# TheRightHandPathSVG.net
KiCad netlist of a schematic drawn in EAGLE
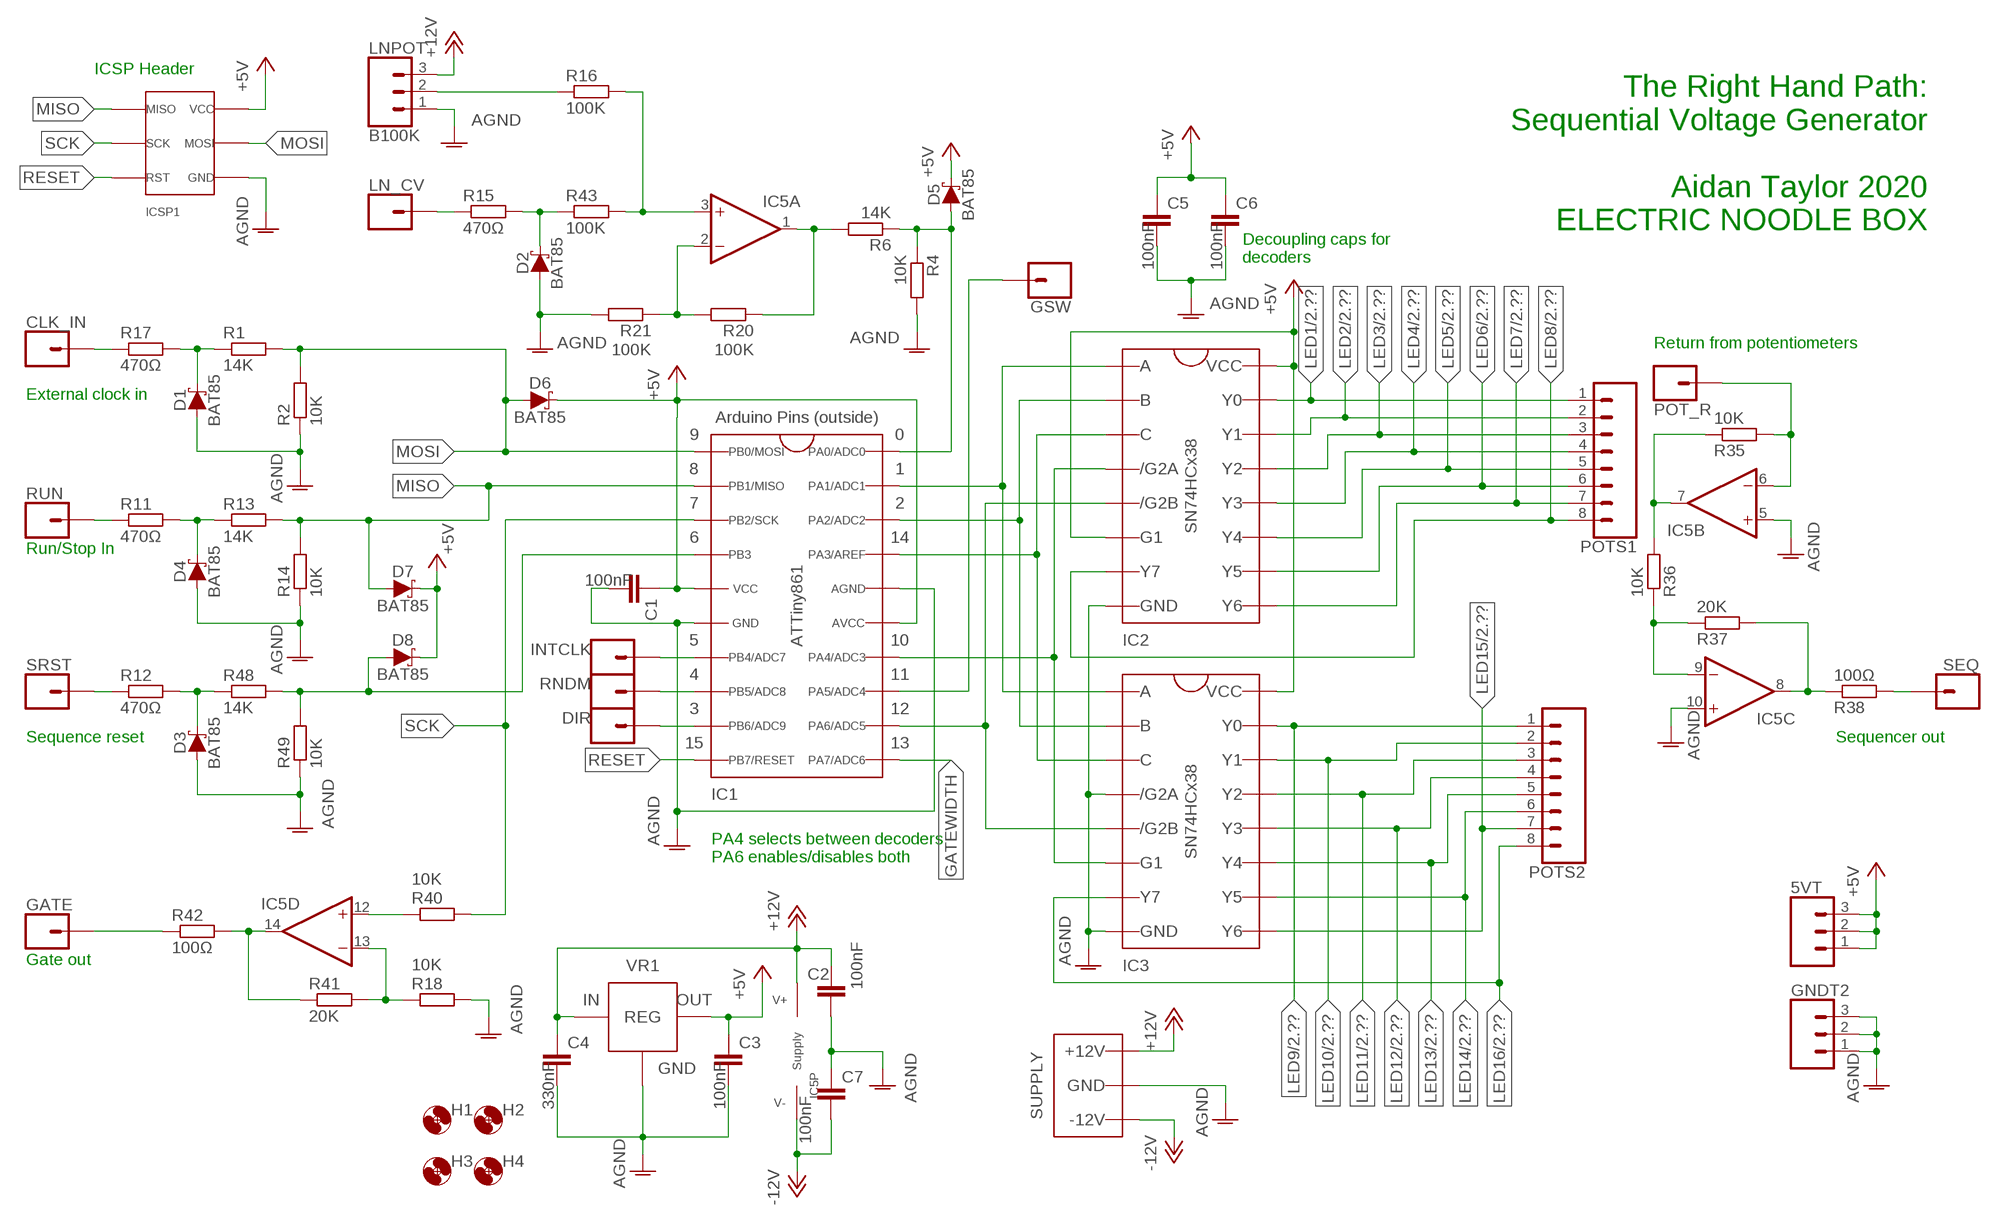
[diagram p0: schematic, sheet 1]
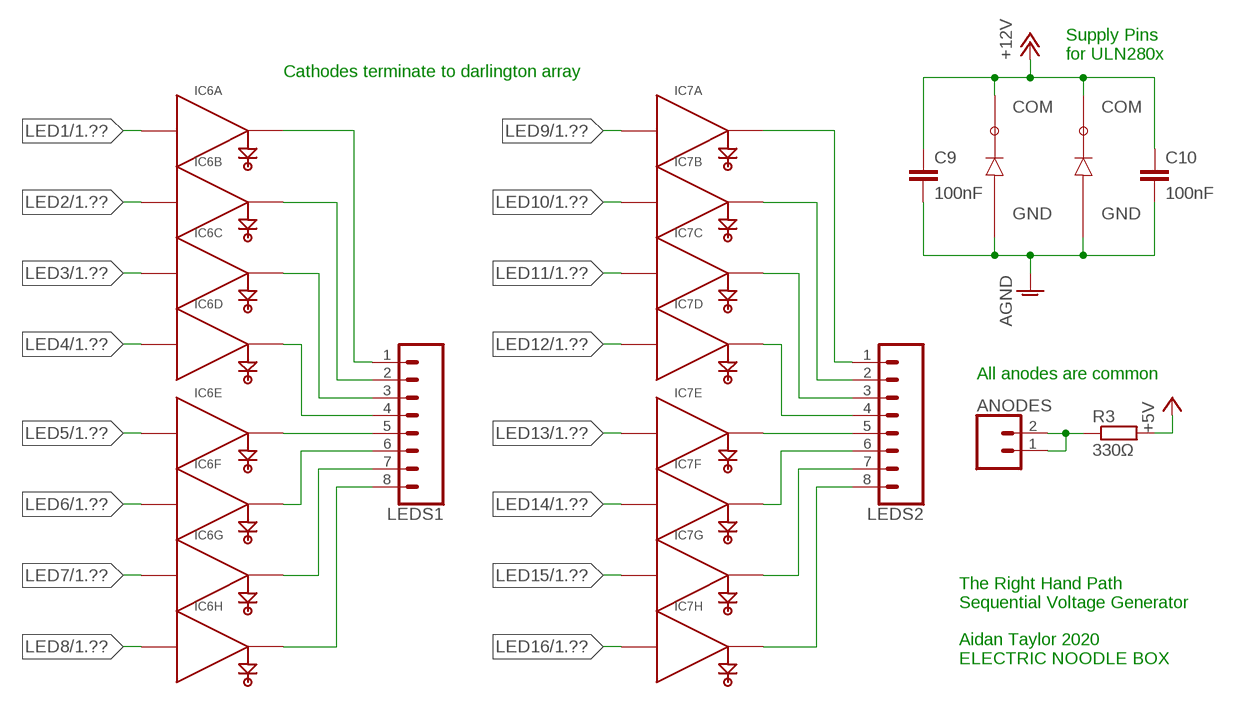
[diagram p1: schematic, sheet 2]

(export (version "E")
  (design (tool "Eeschema 10.0.6"))
  (components
    (comp (ref "5VT")
      (value "3XWIREPAD")
      (footprint "eagle-import:1X03")
      (libsource (lib "eagle-import") (part "3XWIREPAD"))
    )
    (comp (ref "C1")
      (value "100nF")
      (footprint "eagle-import:C050-025X075")
      (libsource (lib "eagle-import") (part "C-EU050-025X075"))
    )
    (comp (ref "C2")
      (value "100nF")
      (footprint "eagle-import:C050-025X075")
      (libsource (lib "eagle-import") (part "C-EU050-025X075"))
    )
    (comp (ref "C3")
      (value "100nF")
      (footprint "eagle-import:C050-025X075")
      (libsource (lib "eagle-import") (part "C-EU050-025X075"))
    )
    (comp (ref "C4")
      (value "330nF")
      (footprint "eagle-import:C050-025X075")
      (libsource (lib "eagle-import") (part "C-EU050-025X075"))
    )
    (comp (ref "C5")
      (value "100nF")
      (footprint "eagle-import:C050-025X075")
      (libsource (lib "eagle-import") (part "C-EU050-025X075"))
    )
    (comp (ref "C6")
      (value "100nF")
      (footprint "eagle-import:C050-025X075")
      (libsource (lib "eagle-import") (part "C-EU050-025X075"))
    )
    (comp (ref "C7")
      (value "100nF")
      (footprint "eagle-import:C050-025X075")
      (libsource (lib "eagle-import") (part "C-EU050-025X075"))
    )
    (comp (ref "CLK_IN")
      (value "1XWIREPAD")
      (footprint "eagle-import:1X01")
      (libsource (lib "eagle-import") (part "1XWIREPAD"))
    )
    (comp (ref "D1")
      (value "BAT85")
      (footprint "eagle-import:DO35-7")
      (libsource (lib "eagle-import") (part "SCHOTTKY_DO35"))
    )
    (comp (ref "D2")
      (value "BAT85")
      (footprint "eagle-import:DO35-7")
      (libsource (lib "eagle-import") (part "SCHOTTKY_DO35"))
    )
    (comp (ref "D3")
      (value "BAT85")
      (footprint "eagle-import:DO35-7")
      (libsource (lib "eagle-import") (part "SCHOTTKY_DO35"))
    )
    (comp (ref "D4")
      (value "BAT85")
      (footprint "eagle-import:DO35-7")
      (libsource (lib "eagle-import") (part "SCHOTTKY_DO35"))
    )
    (comp (ref "D5")
      (value "BAT85")
      (footprint "eagle-import:DO35-7")
      (libsource (lib "eagle-import") (part "SCHOTTKY_DO35"))
    )
    (comp (ref "D6")
      (value "BAT85")
      (footprint "eagle-import:DO35-7")
      (libsource (lib "eagle-import") (part "SCHOTTKY_DO35"))
    )
    (comp (ref "D7")
      (value "BAT85")
      (footprint "eagle-import:DO35-7")
      (libsource (lib "eagle-import") (part "SCHOTTKY_DO35"))
    )
    (comp (ref "D8")
      (value "BAT85")
      (footprint "eagle-import:DO35-7")
      (libsource (lib "eagle-import") (part "SCHOTTKY_DO35"))
    )
    (comp (ref "DIR")
      (value "1XWIREPAD")
      (footprint "eagle-import:1X01")
      (libsource (lib "eagle-import") (part "1XWIREPAD"))
    )
    (comp (ref "GATE")
      (value "1XWIREPAD")
      (footprint "eagle-import:1X01")
      (libsource (lib "eagle-import") (part "1XWIREPAD"))
    )
    (comp (ref "GNDT2")
      (value "3XWIREPAD")
      (footprint "eagle-import:1X03")
      (libsource (lib "eagle-import") (part "3XWIREPAD"))
    )
    (comp (ref "GSW")
      (value "1XWIREPAD")
      (footprint "eagle-import:1X01")
      (libsource (lib "eagle-import") (part "1XWIREPAD"))
    )
    (comp (ref "H1")
      (value "MOUNT-HOLE3.2")
      (footprint "eagle-import:3,2")
      (libsource (lib "eagle-import") (part "MOUNT-HOLE3.2"))
    )
    (comp (ref "H2")
      (value "MOUNT-HOLE3.2")
      (footprint "eagle-import:3,2")
      (libsource (lib "eagle-import") (part "MOUNT-HOLE3.2"))
    )
    (comp (ref "H3")
      (value "MOUNT-HOLE3.2")
      (footprint "eagle-import:3,2")
      (libsource (lib "eagle-import") (part "MOUNT-HOLE3.2"))
    )
    (comp (ref "H4")
      (value "MOUNT-HOLE3.2")
      (footprint "eagle-import:3,2")
      (libsource (lib "eagle-import") (part "MOUNT-HOLE3.2"))
    )
    (comp (ref "IC1")
      (value "ATTINY861")
      (footprint "eagle-import:DIL20")
      (libsource (lib "eagle-import") (part "ATTINY861"))
    )
    (comp (ref "IC2")
      (value "SN74HCX38")
      (footprint "eagle-import:DIL16")
      (libsource (lib "eagle-import") (part "SN74HCX38"))
    )
    (comp (ref "IC3")
      (value "SN74HCX38")
      (footprint "eagle-import:DIL16")
      (libsource (lib "eagle-import") (part "SN74HCX38"))
    )
    (comp (ref "IC5")
      (value "TL0X4DIL")
      (footprint "eagle-import:DIL14")
      (libsource (lib "eagle-import") (part "TL0X4DIL"))
    )
    (comp (ref "ICSP1")
      (value "ICSP_2.54")
      (footprint "eagle-import:2X3")
      (libsource (lib "eagle-import") (part "ICSP_2.54"))
    )
    (comp (ref "INTCLK")
      (value "1XWIREPAD")
      (footprint "eagle-import:1X01")
      (libsource (lib "eagle-import") (part "1XWIREPAD"))
    )
    (comp (ref "LNPOT")
      (value "B100K")
      (footprint "eagle-import:1X03")
      (libsource (lib "eagle-import") (part "3XWIREPAD"))
    )
    (comp (ref "LN_CV")
      (value "1XWIREPAD")
      (footprint "eagle-import:1X01")
      (libsource (lib "eagle-import") (part "1XWIREPAD"))
    )
    (comp (ref "POTS1")
      (value "8XWIREPAD")
      (footprint "eagle-import:1X08")
      (libsource (lib "eagle-import") (part "8XWIREPAD"))
    )
    (comp (ref "POTS2")
      (value "8XWIREPAD")
      (footprint "eagle-import:1X08")
      (libsource (lib "eagle-import") (part "8XWIREPAD"))
    )
    (comp (ref "POT_R")
      (value "1XWIREPAD")
      (footprint "eagle-import:1X01")
      (libsource (lib "eagle-import") (part "1XWIREPAD"))
    )
    (comp (ref "R1")
      (value "14K")
      (footprint "eagle-import:0207_10")
      (libsource (lib "eagle-import") (part "R-EU_0207/10"))
    )
    (comp (ref "R2")
      (value "10K")
      (footprint "eagle-import:0207_10")
      (libsource (lib "eagle-import") (part "R-EU_0207/10"))
    )
    (comp (ref "R4")
      (value "10K")
      (footprint "eagle-import:0207_10")
      (libsource (lib "eagle-import") (part "R-EU_0207/10"))
    )
    (comp (ref "R6")
      (value "14K")
      (footprint "eagle-import:0207_10")
      (libsource (lib "eagle-import") (part "R-EU_0207/10"))
    )
    (comp (ref "R11")
      (value "470Ω")
      (footprint "eagle-import:0207_10")
      (libsource (lib "eagle-import") (part "R-EU_0207/10"))
    )
    (comp (ref "R12")
      (value "470Ω")
      (footprint "eagle-import:0207_10")
      (libsource (lib "eagle-import") (part "R-EU_0207/10"))
    )
    (comp (ref "R13")
      (value "14K")
      (footprint "eagle-import:0207_10")
      (libsource (lib "eagle-import") (part "R-EU_0207/10"))
    )
    (comp (ref "R14")
      (value "10K")
      (footprint "eagle-import:0207_10")
      (libsource (lib "eagle-import") (part "R-EU_0207/10"))
    )
    (comp (ref "R15")
      (value "470Ω")
      (footprint "eagle-import:0207_10")
      (libsource (lib "eagle-import") (part "R-EU_0207/10"))
    )
    (comp (ref "R16")
      (value "100K")
      (footprint "eagle-import:0207_10")
      (libsource (lib "eagle-import") (part "R-EU_0207/10"))
    )
    (comp (ref "R17")
      (value "470Ω")
      (footprint "eagle-import:0207_10")
      (libsource (lib "eagle-import") (part "R-EU_0207/10"))
    )
    (comp (ref "R18")
      (value "10K")
      (footprint "eagle-import:0207_10")
      (libsource (lib "eagle-import") (part "R-EU_0207/10"))
    )
    (comp (ref "R20")
      (value "100K")
      (footprint "eagle-import:0207_10")
      (libsource (lib "eagle-import") (part "R-EU_0207/10"))
    )
    (comp (ref "R21")
      (value "100K")
      (footprint "eagle-import:0207_10")
      (libsource (lib "eagle-import") (part "R-EU_0207/10"))
    )
    (comp (ref "R35")
      (value "10K")
      (footprint "eagle-import:0207_10")
      (libsource (lib "eagle-import") (part "R-EU_0207/10"))
    )
    (comp (ref "R36")
      (value "10K")
      (footprint "eagle-import:0207_10")
      (libsource (lib "eagle-import") (part "R-EU_0207/10"))
    )
    (comp (ref "R37")
      (value "20K")
      (footprint "eagle-import:0207_10")
      (libsource (lib "eagle-import") (part "R-EU_0207/10"))
    )
    (comp (ref "R38")
      (value "100Ω")
      (footprint "eagle-import:0207_10")
      (libsource (lib "eagle-import") (part "R-EU_0207/10"))
    )
    (comp (ref "R40")
      (value "10K")
      (footprint "eagle-import:0207_10")
      (libsource (lib "eagle-import") (part "R-EU_0207/10"))
    )
    (comp (ref "R41")
      (value "20K")
      (footprint "eagle-import:0207_10")
      (libsource (lib "eagle-import") (part "R-EU_0207/10"))
    )
    (comp (ref "R42")
      (value "100Ω")
      (footprint "eagle-import:0207_10")
      (libsource (lib "eagle-import") (part "R-EU_0207/10"))
    )
    (comp (ref "R43")
      (value "100K")
      (footprint "eagle-import:0207_10")
      (libsource (lib "eagle-import") (part "R-EU_0207/10"))
    )
    (comp (ref "R48")
      (value "14K")
      (footprint "eagle-import:0207_10")
      (libsource (lib "eagle-import") (part "R-EU_0207/10"))
    )
    (comp (ref "R49")
      (value "10K")
      (footprint "eagle-import:0207_10")
      (libsource (lib "eagle-import") (part "R-EU_0207/10"))
    )
    (comp (ref "RNDM")
      (value "1XWIREPAD")
      (footprint "eagle-import:1X01")
      (libsource (lib "eagle-import") (part "1XWIREPAD"))
    )
    (comp (ref "RUN")
      (value "1XWIREPAD")
      (footprint "eagle-import:1X01")
      (libsource (lib "eagle-import") (part "1XWIREPAD"))
    )
    (comp (ref "SEQ")
      (value "1XWIREPAD")
      (footprint "eagle-import:1X01")
      (libsource (lib "eagle-import") (part "1XWIREPAD"))
    )
    (comp (ref "SRST")
      (value "1XWIREPAD")
      (footprint "eagle-import:1X01")
      (libsource (lib "eagle-import") (part "1XWIREPAD"))
    )
    (comp (ref "VR1")
      (value "L78L05TO92")
      (footprint "eagle-import:TO92")
      (libsource (lib "eagle-import") (part "L78L05TO92"))
    )
    (comp (ref "WP1")
      (value "COMBO_SUPPLY_HEADER")
      (footprint "eagle-import:COMBINED_POWER")
      (libsource (lib "eagle-import") (part "COMBO_SUPPLY_HEADER"))
    )
    (comp (ref "ANODES")
      (value "2XWIREPAD")
      (footprint "eagle-import:1X02")
      (libsource (lib "eagle-import") (part "2XWIREPAD"))
    )
    (comp (ref "C9")
      (value "100nF")
      (footprint "eagle-import:C050-025X075")
      (libsource (lib "eagle-import") (part "C-EU050-025X075"))
    )
    (comp (ref "C10")
      (value "100nF")
      (footprint "eagle-import:C050-025X075")
      (libsource (lib "eagle-import") (part "C-EU050-025X075"))
    )
    (comp (ref "IC6")
      (value "ULN2801")
      (footprint "eagle-import:DIL18")
      (libsource (lib "eagle-import") (part "ULN2801"))
    )
    (comp (ref "IC7")
      (value "ULN2801")
      (footprint "eagle-import:DIL18")
      (libsource (lib "eagle-import") (part "ULN2801"))
    )
    (comp (ref "LEDS1")
      (value "8XWIREPAD")
      (footprint "eagle-import:1X08")
      (libsource (lib "eagle-import") (part "8XWIREPAD"))
    )
    (comp (ref "LEDS2")
      (value "8XWIREPAD")
      (footprint "eagle-import:1X08")
      (libsource (lib "eagle-import") (part "8XWIREPAD"))
    )
    (comp (ref "R3")
      (value "330Ω")
      (footprint "eagle-import:0207_10")
      (libsource (lib "eagle-import") (part "R-EU_0207/10"))
    )
  )
  (nets
    (net (code "1") (name "+5V") (class "Default")
      (node (ref "5VT") (pin "1") (pinfunction "1_1") (pintype "passive"))
      (node (ref "5VT") (pin "2") (pinfunction "2_2") (pintype "passive"))
      (node (ref "5VT") (pin "3") (pinfunction "3_3") (pintype "passive"))
      (node (ref "C1") (pin "1") (pinfunction "1_1") (pintype "passive"))
      (node (ref "C3") (pin "1") (pinfunction "1_1") (pintype "passive"))
      (node (ref "C5") (pin "1") (pinfunction "1_1") (pintype "passive"))
      (node (ref "C6") (pin "1") (pinfunction "1_1") (pintype "passive"))
      (node (ref "D5") (pin "C") (pinfunction "C_C") (pintype "passive"))
      (node (ref "D6") (pin "C") (pinfunction "C_C") (pintype "passive"))
      (node (ref "D7") (pin "C") (pinfunction "C_C") (pintype "passive"))
      (node (ref "D8") (pin "C") (pinfunction "C_C") (pintype "passive"))
      (node (ref "IC1") (pin "15") (pinfunction "AVCC_15") (pintype "bidirectional"))
      (node (ref "IC1") (pin "5") (pinfunction "VCC_5") (pintype "power_in"))
      (node (ref "IC2") (pin "16") (pinfunction "16_VCC_16") (pintype "power_in"))
      (node (ref "IC2") (pin "6") (pinfunction "6_G1_6") (pintype "input"))
      (node (ref "IC3") (pin "16") (pinfunction "16_VCC_16") (pintype "power_in"))
      (node (ref "ICSP1") (pin "2") (pinfunction "6VCC_2") (pintype "power_in"))
      (node (ref "R3") (pin "2") (pinfunction "2_2") (pintype "passive"))
      (node (ref "VR1") (pin "1") (pinfunction "VOUT_1") (pintype "output"))
    )
    (net (code "2") (name "+12V") (class "Default")
      (node (ref "C10") (pin "1") (pinfunction "1_1") (pintype "passive"))
      (node (ref "C2") (pin "1") (pinfunction "1_1") (pintype "passive"))
      (node (ref "C4") (pin "1") (pinfunction "1_1") (pintype "passive"))
      (node (ref "C9") (pin "1") (pinfunction "1_1") (pintype "passive"))
      (node (ref "IC5") (pin "4") (pinfunction "V+_4") (pintype "bidirectional"))
      (node (ref "IC6") (pin "10") (pinfunction "COM_10") (pintype "power_in"))
      (node (ref "IC7") (pin "10") (pinfunction "COM_10") (pintype "power_in"))
      (node (ref "LNPOT") (pin "3") (pinfunction "3_3") (pintype "passive"))
      (node (ref "VR1") (pin "3") (pinfunction "VIN_3") (pintype "input"))
      (node (ref "WP1") (pin "V+1") (pinfunction "V++_V+1") (pintype "power_in"))
      (node (ref "WP1") (pin "V+2") (pinfunction "V++_V+2") (pintype "power_in"))
      (node (ref "WP1") (pin "V+3") (pinfunction "V++_V+3") (pintype "power_in"))
    )
    (net (code "3") (name "-12V") (class "Default")
      (node (ref "C7") (pin "2") (pinfunction "2_2") (pintype "passive"))
      (node (ref "IC5") (pin "11") (pinfunction "V-_11") (pintype "bidirectional"))
      (node (ref "WP1") (pin "V-1") (pinfunction "V--_V-1") (pintype "power_in"))
      (node (ref "WP1") (pin "V-2") (pinfunction "V--_V-2") (pintype "power_in"))
      (node (ref "WP1") (pin "V-3") (pinfunction "V--_V-3") (pintype "power_in"))
    )
    (net (code "4") (name "AGND") (class "Default")
      (node (ref "C1") (pin "2") (pinfunction "2_2") (pintype "passive"))
      (node (ref "C10") (pin "2") (pinfunction "2_2") (pintype "passive"))
      (node (ref "C2") (pin "2") (pinfunction "2_2") (pintype "passive"))
      (node (ref "C3") (pin "2") (pinfunction "2_2") (pintype "passive"))
      (node (ref "C4") (pin "2") (pinfunction "2_2") (pintype "passive"))
      (node (ref "C5") (pin "2") (pinfunction "2_2") (pintype "passive"))
      (node (ref "C6") (pin "2") (pinfunction "2_2") (pintype "passive"))
      (node (ref "C7") (pin "1") (pinfunction "1_1") (pintype "passive"))
      (node (ref "C9") (pin "2") (pinfunction "2_2") (pintype "passive"))
      (node (ref "D1") (pin "A") (pinfunction "A_A") (pintype "passive"))
      (node (ref "D2") (pin "A") (pinfunction "A_A") (pintype "passive"))
      (node (ref "D3") (pin "A") (pinfunction "A_A") (pintype "passive"))
      (node (ref "D4") (pin "A") (pinfunction "A_A") (pintype "passive"))
      (node (ref "GNDT2") (pin "1") (pinfunction "1_1") (pintype "passive"))
      (node (ref "GNDT2") (pin "2") (pinfunction "2_2") (pintype "passive"))
      (node (ref "GNDT2") (pin "3") (pinfunction "3_3") (pintype "passive"))
      (node (ref "IC1") (pin "16") (pinfunction "AGND_16") (pintype "bidirectional"))
      (node (ref "IC1") (pin "6") (pinfunction "GND_6") (pintype "power_in"))
      (node (ref "IC2") (pin "8") (pinfunction "8_GND_8") (pintype "power_in"))
      (node (ref "IC3") (pin "4") (pinfunction "4_/G2A_4") (pintype "input"))
      (node (ref "IC3") (pin "8") (pinfunction "8_GND_8") (pintype "power_in"))
      (node (ref "IC5") (pin "10") (pinfunction "+IN_10") (pintype "input"))
      (node (ref "IC5") (pin "5") (pinfunction "+IN_5") (pintype "input"))
      (node (ref "IC6") (pin "9") (pinfunction "GND_9") (pintype "power_in"))
      (node (ref "IC7") (pin "9") (pinfunction "GND_9") (pintype "power_in"))
      (node (ref "ICSP1") (pin "6") (pinfunction "4GND_6") (pintype "power_in"))
      (node (ref "LNPOT") (pin "1") (pinfunction "1_1") (pintype "passive"))
      (node (ref "R14") (pin "1") (pinfunction "1_1") (pintype "passive"))
      (node (ref "R18") (pin "2") (pinfunction "2_2") (pintype "passive"))
      (node (ref "R2") (pin "1") (pinfunction "1_1") (pintype "passive"))
      (node (ref "R21") (pin "2") (pinfunction "2_2") (pintype "passive"))
      (node (ref "R4") (pin "2") (pinfunction "2_2") (pintype "passive"))
      (node (ref "R49") (pin "1") (pinfunction "1_1") (pintype "passive"))
      (node (ref "VR1") (pin "2") (pinfunction "GND_2") (pintype "power_in"))
      (node (ref "WP1") (pin "GND1") (pinfunction "AGND_GND1") (pintype "power_in"))
      (node (ref "WP1") (pin "GND2") (pinfunction "AGND_GND2") (pintype "power_in"))
      (node (ref "WP1") (pin "GND3") (pinfunction "AGND_GND3") (pintype "power_in"))
      (node (ref "WP1") (pin "GND4") (pinfunction "AGND_GND4") (pintype "power_in"))
      (node (ref "WP1") (pin "GND5") (pinfunction "AGND_GND5") (pintype "power_in"))
      (node (ref "WP1") (pin "GND6") (pinfunction "AGND_GND6") (pintype "power_in"))
      (node (ref "WP1") (pin "GND7") (pinfunction "AGND_GND7") (pintype "power_in"))
      (node (ref "WP1") (pin "GND8") (pinfunction "AGND_GND8") (pintype "power_in"))
    )
    (net (code "5") (name "GATEWIDTH") (class "Default")
      (node (ref "IC1") (pin "11") (pinfunction "11_PA7_11") (pintype "bidirectional"))
    )
    (net (code "6") (name "LED1") (class "Default")
      (node (ref "IC2") (pin "15") (pinfunction "15_Y0_15") (pintype "output"))
      (node (ref "IC6") (pin "1") (pinfunction "IN_1") (pintype "input"))
      (node (ref "POTS1") (pin "1") (pinfunction "1_1") (pintype "passive"))
    )
    (net (code "7") (name "LED2") (class "Default")
      (node (ref "IC2") (pin "14") (pinfunction "14_Y1_14") (pintype "output"))
      (node (ref "IC6") (pin "2") (pinfunction "IN_2") (pintype "input"))
      (node (ref "POTS1") (pin "2") (pinfunction "2_2") (pintype "passive"))
    )
    (net (code "8") (name "LED3") (class "Default")
      (node (ref "IC2") (pin "13") (pinfunction "13_Y2_13") (pintype "output"))
      (node (ref "IC6") (pin "3") (pinfunction "IN_3") (pintype "input"))
      (node (ref "POTS1") (pin "3") (pinfunction "3_3") (pintype "passive"))
    )
    (net (code "9") (name "LED4") (class "Default")
      (node (ref "IC2") (pin "12") (pinfunction "12_Y3_12") (pintype "output"))
      (node (ref "IC6") (pin "4") (pinfunction "IN_4") (pintype "input"))
      (node (ref "POTS1") (pin "4") (pinfunction "4_4") (pintype "passive"))
    )
    (net (code "10") (name "LED5") (class "Default")
      (node (ref "IC2") (pin "11") (pinfunction "11_Y4_11") (pintype "output"))
      (node (ref "IC6") (pin "5") (pinfunction "IN_5") (pintype "input"))
      (node (ref "POTS1") (pin "5") (pinfunction "5_5") (pintype "passive"))
    )
    (net (code "11") (name "LED6") (class "Default")
      (node (ref "IC2") (pin "10") (pinfunction "10_Y5_10") (pintype "output"))
      (node (ref "IC6") (pin "6") (pinfunction "IN_6") (pintype "input"))
      (node (ref "POTS1") (pin "6") (pinfunction "6_6") (pintype "passive"))
    )
    (net (code "12") (name "LED7") (class "Default")
      (node (ref "IC2") (pin "9") (pinfunction "9_Y6_9") (pintype "output"))
      (node (ref "IC6") (pin "7") (pinfunction "IN_7") (pintype "input"))
      (node (ref "POTS1") (pin "7") (pinfunction "7_7") (pintype "passive"))
    )
    (net (code "13") (name "LED8") (class "Default")
      (node (ref "IC2") (pin "7") (pinfunction "7_Y7_7") (pintype "output"))
      (node (ref "IC6") (pin "8") (pinfunction "IN_8") (pintype "input"))
      (node (ref "POTS1") (pin "8") (pinfunction "8_8") (pintype "passive"))
    )
    (net (code "14") (name "LED9") (class "Default")
      (node (ref "IC3") (pin "15") (pinfunction "15_Y0_15") (pintype "output"))
      (node (ref "IC7") (pin "1") (pinfunction "IN_1") (pintype "input"))
      (node (ref "POTS2") (pin "1") (pinfunction "1_1") (pintype "passive"))
    )
    (net (code "15") (name "LED10") (class "Default")
      (node (ref "IC3") (pin "14") (pinfunction "14_Y1_14") (pintype "output"))
      (node (ref "IC7") (pin "2") (pinfunction "IN_2") (pintype "input"))
      (node (ref "POTS2") (pin "2") (pinfunction "2_2") (pintype "passive"))
    )
    (net (code "16") (name "LED11") (class "Default")
      (node (ref "IC3") (pin "13") (pinfunction "13_Y2_13") (pintype "output"))
      (node (ref "IC7") (pin "3") (pinfunction "IN_3") (pintype "input"))
      (node (ref "POTS2") (pin "3") (pinfunction "3_3") (pintype "passive"))
    )
    (net (code "17") (name "LED12") (class "Default")
      (node (ref "IC3") (pin "12") (pinfunction "12_Y3_12") (pintype "output"))
      (node (ref "IC7") (pin "4") (pinfunction "IN_4") (pintype "input"))
      (node (ref "POTS2") (pin "4") (pinfunction "4_4") (pintype "passive"))
    )
    (net (code "18") (name "LED13") (class "Default")
      (node (ref "IC3") (pin "11") (pinfunction "11_Y4_11") (pintype "output"))
      (node (ref "IC7") (pin "5") (pinfunction "IN_5") (pintype "input"))
      (node (ref "POTS2") (pin "5") (pinfunction "5_5") (pintype "passive"))
    )
    (net (code "19") (name "LED14") (class "Default")
      (node (ref "IC3") (pin "10") (pinfunction "10_Y5_10") (pintype "output"))
      (node (ref "IC7") (pin "6") (pinfunction "IN_6") (pintype "input"))
      (node (ref "POTS2") (pin "6") (pinfunction "6_6") (pintype "passive"))
    )
    (net (code "20") (name "LED15") (class "Default")
      (node (ref "IC3") (pin "9") (pinfunction "9_Y6_9") (pintype "output"))
      (node (ref "IC7") (pin "7") (pinfunction "IN_7") (pintype "input"))
      (node (ref "POTS2") (pin "7") (pinfunction "7_7") (pintype "passive"))
    )
    (net (code "21") (name "LED16") (class "Default")
      (node (ref "IC3") (pin "7") (pinfunction "7_Y7_7") (pintype "output"))
      (node (ref "IC7") (pin "8") (pinfunction "IN_8") (pintype "input"))
      (node (ref "POTS2") (pin "8") (pinfunction "8_8") (pintype "passive"))
    )
    (net (code "22") (name "MISO") (class "Default")
      (node (ref "D7") (pin "A") (pinfunction "A_A") (pintype "passive"))
      (node (ref "IC1") (pin "2") (pinfunction "2_PB1_2") (pintype "bidirectional"))
      (node (ref "ICSP1") (pin "1") (pinfunction "1MISO_1") (pintype "bidirectional"))
      (node (ref "R13") (pin "2") (pinfunction "2_2") (pintype "passive"))
      (node (ref "R14") (pin "2") (pinfunction "2_2") (pintype "passive"))
    )
    (net (code "23") (name "MOSI") (class "Default")
      (node (ref "D6") (pin "A") (pinfunction "A_A") (pintype "passive"))
      (node (ref "IC1") (pin "1") (pinfunction "1_PB0_1") (pintype "bidirectional"))
      (node (ref "ICSP1") (pin "4") (pinfunction "5MOSI_4") (pintype "bidirectional"))
      (node (ref "R1") (pin "2") (pinfunction "2_2") (pintype "passive"))
      (node (ref "R2") (pin "2") (pinfunction "2_2") (pintype "passive"))
    )
    (net (code "24") (name "Net-(ANODES-Pad1)") (class "Default")
      (node (ref "ANODES") (pin "1") (pinfunction "1_1") (pintype "passive"))
      (node (ref "ANODES") (pin "2") (pinfunction "2_2") (pintype "passive"))
      (node (ref "R3") (pin "1") (pinfunction "1_1") (pintype "passive"))
    )
    (net (code "25") (name "Net-(CLK_IN-Pad1)") (class "Default")
      (node (ref "CLK_IN") (pin "1") (pinfunction "1_1") (pintype "passive"))
      (node (ref "R17") (pin "1") (pinfunction "1_1") (pintype "passive"))
    )
    (net (code "26") (name "Net-(D1-PadC)") (class "Default")
      (node (ref "D1") (pin "C") (pinfunction "C_C") (pintype "passive"))
      (node (ref "R1") (pin "1") (pinfunction "1_1") (pintype "passive"))
      (node (ref "R17") (pin "2") (pinfunction "2_2") (pintype "passive"))
    )
    (net (code "27") (name "Net-(D2-PadC)") (class "Default")
      (node (ref "D2") (pin "C") (pinfunction "C_C") (pintype "passive"))
      (node (ref "R15") (pin "2") (pinfunction "2_2") (pintype "passive"))
      (node (ref "R43") (pin "1") (pinfunction "1_1") (pintype "passive"))
    )
    (net (code "28") (name "Net-(D3-PadC)") (class "Default")
      (node (ref "D3") (pin "C") (pinfunction "C_C") (pintype "passive"))
      (node (ref "R12") (pin "2") (pinfunction "2_2") (pintype "passive"))
      (node (ref "R48") (pin "1") (pinfunction "1_1") (pintype "passive"))
    )
    (net (code "29") (name "Net-(D4-PadC)") (class "Default")
      (node (ref "D4") (pin "C") (pinfunction "C_C") (pintype "passive"))
      (node (ref "R11") (pin "2") (pinfunction "2_2") (pintype "passive"))
      (node (ref "R13") (pin "1") (pinfunction "1_1") (pintype "passive"))
    )
    (net (code "30") (name "Net-(GATE-Pad1)") (class "Default")
      (node (ref "GATE") (pin "1") (pinfunction "1_1") (pintype "passive"))
      (node (ref "R42") (pin "1") (pinfunction "1_1") (pintype "passive"))
    )
    (net (code "31") (name "Net-(IC1-4_PB3)") (class "Default")
      (node (ref "D8") (pin "A") (pinfunction "A_A") (pintype "passive"))
      (node (ref "IC1") (pin "4") (pinfunction "4_PB3_4") (pintype "bidirectional"))
      (node (ref "R48") (pin "2") (pinfunction "2_2") (pintype "passive"))
      (node (ref "R49") (pin "2") (pinfunction "2_2") (pintype "passive"))
    )
    (net (code "32") (name "Net-(IC1-7_PB4)") (class "Default")
      (node (ref "IC1") (pin "7") (pinfunction "7_PB4_7") (pintype "bidirectional"))
      (node (ref "INTCLK") (pin "1") (pinfunction "1_1") (pintype "passive"))
    )
    (net (code "33") (name "Net-(IC1-8_PB5)") (class "Default")
      (node (ref "IC1") (pin "8") (pinfunction "8_PB5_8") (pintype "bidirectional"))
      (node (ref "RNDM") (pin "1") (pinfunction "1_1") (pintype "passive"))
    )
    (net (code "34") (name "Net-(IC1-9_PB6)") (class "Default")
      (node (ref "DIR") (pin "1") (pinfunction "1_1") (pintype "passive"))
      (node (ref "IC1") (pin "9") (pinfunction "9_PB6_9") (pintype "bidirectional"))
    )
    (net (code "35") (name "Net-(IC1-12_PA6)") (class "Default")
      (node (ref "IC1") (pin "12") (pinfunction "12_PA6_12") (pintype "bidirectional"))
      (node (ref "IC2") (pin "5") (pinfunction "5_/G2B_5") (pintype "input"))
      (node (ref "IC3") (pin "5") (pinfunction "5_/G2B_5") (pintype "input"))
    )
    (net (code "36") (name "Net-(IC1-13_PA5)") (class "Default")
      (node (ref "GSW") (pin "1") (pinfunction "1_1") (pintype "passive"))
      (node (ref "IC1") (pin "13") (pinfunction "13_PA5_13") (pintype "bidirectional"))
    )
    (net (code "37") (name "Net-(IC1-14_PA4)") (class "Default")
      (node (ref "IC1") (pin "14") (pinfunction "14_PA4_14") (pintype "bidirectional"))
      (node (ref "IC2") (pin "4") (pinfunction "4_/G2A_4") (pintype "input"))
      (node (ref "IC3") (pin "6") (pinfunction "6_G1_6") (pintype "input"))
    )
    (net (code "38") (name "Net-(IC1-17_PA3)") (class "Default")
      (node (ref "IC1") (pin "17") (pinfunction "17_PA3_17") (pintype "bidirectional"))
      (node (ref "IC2") (pin "3") (pinfunction "3_C_3") (pintype "input"))
      (node (ref "IC3") (pin "3") (pinfunction "3_C_3") (pintype "input"))
    )
    (net (code "39") (name "Net-(IC1-18_PA2)") (class "Default")
      (node (ref "IC1") (pin "18") (pinfunction "18_PA2_18") (pintype "bidirectional"))
      (node (ref "IC2") (pin "2") (pinfunction "2_B_2") (pintype "input"))
      (node (ref "IC3") (pin "2") (pinfunction "2_B_2") (pintype "input"))
    )
    (net (code "40") (name "Net-(IC1-19_PA1)") (class "Default")
      (node (ref "IC1") (pin "19") (pinfunction "19_PA1_19") (pintype "bidirectional"))
      (node (ref "IC2") (pin "1") (pinfunction "1_A_1") (pintype "input"))
      (node (ref "IC3") (pin "1") (pinfunction "1_A_1") (pintype "input"))
    )
    (net (code "41") (name "Net-(IC1-20_PA0)") (class "Default")
      (node (ref "D5") (pin "A") (pinfunction "A_A") (pintype "passive"))
      (node (ref "IC1") (pin "20") (pinfunction "20_PA0_20") (pintype "bidirectional"))
      (node (ref "R4") (pin "1") (pinfunction "1_1") (pintype "passive"))
      (node (ref "R6") (pin "1") (pinfunction "1_1") (pintype "passive"))
    )
    (net (code "42") (name "Net-(IC5A-+IN)") (class "Default")
      (node (ref "IC5") (pin "3") (pinfunction "+IN_3") (pintype "input"))
      (node (ref "R16") (pin "2") (pinfunction "2_2") (pintype "passive"))
      (node (ref "R43") (pin "2") (pinfunction "2_2") (pintype "passive"))
    )
    (net (code "43") (name "Net-(IC5A--IN)") (class "Default")
      (node (ref "IC5") (pin "2") (pinfunction "-IN_2") (pintype "input"))
      (node (ref "R20") (pin "2") (pinfunction "2_2") (pintype "passive"))
      (node (ref "R21") (pin "1") (pinfunction "1_1") (pintype "passive"))
    )
    (net (code "44") (name "Net-(IC5A-OUT)") (class "Default")
      (node (ref "IC5") (pin "1") (pinfunction "OUT_1") (pintype "output"))
      (node (ref "R20") (pin "1") (pinfunction "1_1") (pintype "passive"))
      (node (ref "R6") (pin "2") (pinfunction "2_2") (pintype "passive"))
    )
    (net (code "45") (name "Net-(IC5B--IN)") (class "Default")
      (node (ref "IC5") (pin "6") (pinfunction "-IN_6") (pintype "input"))
      (node (ref "POT_R") (pin "1") (pinfunction "1_1") (pintype "passive"))
      (node (ref "R35") (pin "2") (pinfunction "2_2") (pintype "passive"))
    )
    (net (code "46") (name "Net-(IC5B-OUT)") (class "Default")
      (node (ref "IC5") (pin "7") (pinfunction "OUT_7") (pintype "output"))
      (node (ref "R35") (pin "1") (pinfunction "1_1") (pintype "passive"))
      (node (ref "R36") (pin "2") (pinfunction "2_2") (pintype "passive"))
    )
    (net (code "47") (name "Net-(IC5C--IN)") (class "Default")
      (node (ref "IC5") (pin "9") (pinfunction "-IN_9") (pintype "input"))
      (node (ref "R36") (pin "1") (pinfunction "1_1") (pintype "passive"))
      (node (ref "R37") (pin "1") (pinfunction "1_1") (pintype "passive"))
    )
    (net (code "48") (name "Net-(IC5C-OUT)") (class "Default")
      (node (ref "IC5") (pin "8") (pinfunction "OUT_8") (pintype "output"))
      (node (ref "R37") (pin "2") (pinfunction "2_2") (pintype "passive"))
      (node (ref "R38") (pin "1") (pinfunction "1_1") (pintype "passive"))
    )
    (net (code "49") (name "Net-(IC5D-+IN)") (class "Default")
      (node (ref "IC5") (pin "12") (pinfunction "+IN_12") (pintype "input"))
      (node (ref "R40") (pin "1") (pinfunction "1_1") (pintype "passive"))
    )
    (net (code "50") (name "Net-(IC5D--IN)") (class "Default")
      (node (ref "IC5") (pin "13") (pinfunction "-IN_13") (pintype "input"))
      (node (ref "R18") (pin "1") (pinfunction "1_1") (pintype "passive"))
      (node (ref "R41") (pin "2") (pinfunction "2_2") (pintype "passive"))
    )
    (net (code "51") (name "Net-(IC5D-OUT)") (class "Default")
      (node (ref "IC5") (pin "14") (pinfunction "OUT_14") (pintype "output"))
      (node (ref "R41") (pin "1") (pinfunction "1_1") (pintype "passive"))
      (node (ref "R42") (pin "2") (pinfunction "2_2") (pintype "passive"))
    )
    (net (code "52") (name "Net-(IC6A-P$2)") (class "Default")
      (node (ref "IC6") (pin "18") (pinfunction "P$2_18") (pintype "output"))
      (node (ref "LEDS1") (pin "1") (pinfunction "1_1") (pintype "passive"))
    )
    (net (code "53") (name "Net-(IC6B-P$2)") (class "Default")
      (node (ref "IC6") (pin "17") (pinfunction "P$2_17") (pintype "output"))
      (node (ref "LEDS1") (pin "2") (pinfunction "2_2") (pintype "passive"))
    )
    (net (code "54") (name "Net-(IC6C-P$2)") (class "Default")
      (node (ref "IC6") (pin "16") (pinfunction "P$2_16") (pintype "output"))
      (node (ref "LEDS1") (pin "3") (pinfunction "3_3") (pintype "passive"))
    )
    (net (code "55") (name "Net-(IC6D-P$2)") (class "Default")
      (node (ref "IC6") (pin "15") (pinfunction "P$2_15") (pintype "output"))
      (node (ref "LEDS1") (pin "4") (pinfunction "4_4") (pintype "passive"))
    )
    (net (code "56") (name "Net-(IC6E-P$2)") (class "Default")
      (node (ref "IC6") (pin "14") (pinfunction "P$2_14") (pintype "output"))
      (node (ref "LEDS1") (pin "5") (pinfunction "5_5") (pintype "passive"))
    )
    (net (code "57") (name "Net-(IC6F-P$2)") (class "Default")
      (node (ref "IC6") (pin "13") (pinfunction "P$2_13") (pintype "output"))
      (node (ref "LEDS1") (pin "6") (pinfunction "6_6") (pintype "passive"))
    )
    (net (code "58") (name "Net-(IC6G-P$2)") (class "Default")
      (node (ref "IC6") (pin "12") (pinfunction "P$2_12") (pintype "output"))
      (node (ref "LEDS1") (pin "7") (pinfunction "7_7") (pintype "passive"))
    )
    (net (code "59") (name "Net-(IC6I-P$2)") (class "Default")
      (node (ref "IC6") (pin "11") (pinfunction "P$2_11") (pintype "output"))
      (node (ref "LEDS1") (pin "8") (pinfunction "8_8") (pintype "passive"))
    )
    (net (code "60") (name "Net-(IC7A-P$2)") (class "Default")
      (node (ref "IC7") (pin "18") (pinfunction "P$2_18") (pintype "output"))
      (node (ref "LEDS2") (pin "1") (pinfunction "1_1") (pintype "passive"))
    )
    (net (code "61") (name "Net-(IC7B-P$2)") (class "Default")
      (node (ref "IC7") (pin "17") (pinfunction "P$2_17") (pintype "output"))
      (node (ref "LEDS2") (pin "2") (pinfunction "2_2") (pintype "passive"))
    )
    (net (code "62") (name "Net-(IC7C-P$2)") (class "Default")
      (node (ref "IC7") (pin "16") (pinfunction "P$2_16") (pintype "output"))
      (node (ref "LEDS2") (pin "3") (pinfunction "3_3") (pintype "passive"))
    )
    (net (code "63") (name "Net-(IC7D-P$2)") (class "Default")
      (node (ref "IC7") (pin "15") (pinfunction "P$2_15") (pintype "output"))
      (node (ref "LEDS2") (pin "4") (pinfunction "4_4") (pintype "passive"))
    )
    (net (code "64") (name "Net-(IC7E-P$2)") (class "Default")
      (node (ref "IC7") (pin "14") (pinfunction "P$2_14") (pintype "output"))
      (node (ref "LEDS2") (pin "5") (pinfunction "5_5") (pintype "passive"))
    )
    (net (code "65") (name "Net-(IC7F-P$2)") (class "Default")
      (node (ref "IC7") (pin "13") (pinfunction "P$2_13") (pintype "output"))
      (node (ref "LEDS2") (pin "6") (pinfunction "6_6") (pintype "passive"))
    )
    (net (code "66") (name "Net-(IC7G-P$2)") (class "Default")
      (node (ref "IC7") (pin "12") (pinfunction "P$2_12") (pintype "output"))
      (node (ref "LEDS2") (pin "7") (pinfunction "7_7") (pintype "passive"))
    )
    (net (code "67") (name "Net-(IC7I-P$2)") (class "Default")
      (node (ref "IC7") (pin "11") (pinfunction "P$2_11") (pintype "output"))
      (node (ref "LEDS2") (pin "8") (pinfunction "8_8") (pintype "passive"))
    )
    (net (code "68") (name "Net-(LNPOT-Pad2)") (class "Default")
      (node (ref "LNPOT") (pin "2") (pinfunction "2_2") (pintype "passive"))
      (node (ref "R16") (pin "1") (pinfunction "1_1") (pintype "passive"))
    )
    (net (code "69") (name "Net-(LN_CV-Pad1)") (class "Default")
      (node (ref "LN_CV") (pin "1") (pinfunction "1_1") (pintype "passive"))
      (node (ref "R15") (pin "1") (pinfunction "1_1") (pintype "passive"))
    )
    (net (code "70") (name "Net-(R11-Pad1)") (class "Default")
      (node (ref "R11") (pin "1") (pinfunction "1_1") (pintype "passive"))
      (node (ref "RUN") (pin "1") (pinfunction "1_1") (pintype "passive"))
    )
    (net (code "71") (name "Net-(R12-Pad1)") (class "Default")
      (node (ref "R12") (pin "1") (pinfunction "1_1") (pintype "passive"))
      (node (ref "SRST") (pin "1") (pinfunction "1_1") (pintype "passive"))
    )
    (net (code "72") (name "Net-(R38-Pad2)") (class "Default")
      (node (ref "R38") (pin "2") (pinfunction "2_2") (pintype "passive"))
      (node (ref "SEQ") (pin "1") (pinfunction "1_1") (pintype "passive"))
    )
    (net (code "73") (name "RESET") (class "Default")
      (node (ref "IC1") (pin "10") (pinfunction "10_PB7_10") (pintype "bidirectional"))
      (node (ref "ICSP1") (pin "5") (pinfunction "3RST_5") (pintype "bidirectional"))
    )
    (net (code "74") (name "SCK") (class "Default")
      (node (ref "IC1") (pin "3") (pinfunction "3_PB2_3") (pintype "bidirectional"))
      (node (ref "ICSP1") (pin "3") (pinfunction "2SCK_3") (pintype "bidirectional"))
      (node (ref "R40") (pin "2") (pinfunction "2_2") (pintype "passive"))
    )
  )
)
